# FTDI.net
KiCad netlist of a schematic drawn in Altium Designer
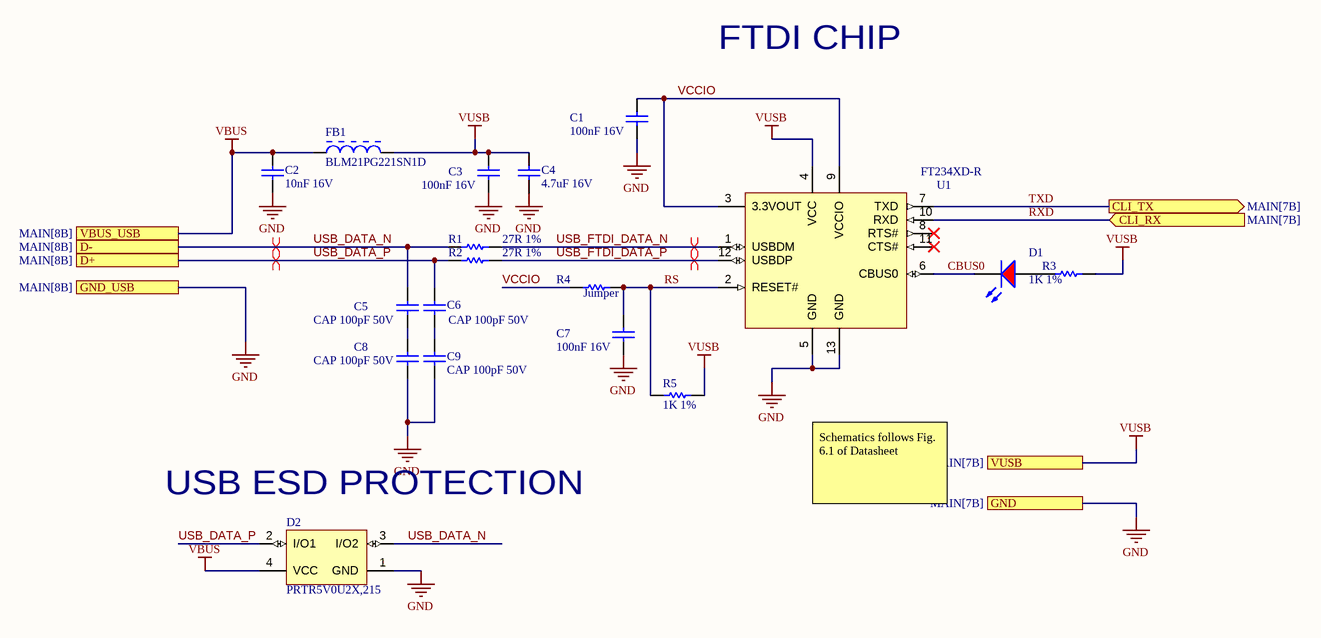
[diagram p0: FTDI.SchDoc]

(export (version "E")
  (design (tool "Eeschema 10.0.6"))
  (components
    (comp (ref "C1")
      (value "100nF 16V")
      (footprint "CAPC0603(1608)100_N")
      (description "CAP 100nF 16V ±10% 0603 (1608 Metric) Thickness 1mm SMD")
      (fields (field (name "TOLERANCE") "Â±10%"))
      (libsource (lib "Altium Content Vault") (part "CAP"))
    )
    (comp (ref "C2")
      (value "10nF 16V")
      (footprint "CAPC0603(1608)100_N")
      (description "CAP 10nF 16V ±10% 0603 (1608 Metric) Thickness 1mm SMD")
      (fields (field (name "TOLERANCE") "Â±10%"))
      (libsource (lib "Altium Content Vault") (part "CAP"))
    )
    (comp (ref "C3")
      (value "100nF 16V")
      (footprint "CAPC0603(1608)100_N")
      (description "CAP 100nF 16V ±10% 0603 (1608 Metric) Thickness 1mm SMD")
      (fields (field (name "TOLERANCE") "Â±10%"))
      (libsource (lib "Altium Content Vault") (part "CAP"))
    )
    (comp (ref "C4")
      (value "4.7uF 16V")
      (footprint "CAPC0805(2012)145_N")
      (description "CAP 4.7uF 16V -20% to +80% 0805 (2012 Metric) Thickness 1.45mm SMD")
      (fields (field (name "TOLERANCE") "-20% to +80%"))
      (libsource (lib "Altium Content Vault") (part "CAP"))
    )
    (comp (ref "C5")
      (value "CAP 100pF 50V")
      (footprint "CAPC0603(1608)100_L")
      (description "CAP 100pF 50V ±20% 0603 (1608 Metric) Thickness 1mm SMD")
      (fields (field (name "TOLERANCE") "Â±20%"))
      (libsource (lib "Altium Content Vault") (part "CAP"))
    )
    (comp (ref "C6")
      (value "CAP 100pF 50V")
      (footprint "CAPC0603(1608)100_L")
      (description "CAP 100pF 50V ±20% 0603 (1608 Metric) Thickness 1mm SMD")
      (fields (field (name "TOLERANCE") "Â±20%"))
      (libsource (lib "Altium Content Vault") (part "CAP"))
    )
    (comp (ref "C7")
      (value "100nF 16V")
      (footprint "CAPC0603(1608)100_N")
      (description "CAP 100nF 16V ±10% 0603 (1608 Metric) Thickness 1mm SMD")
      (fields (field (name "TOLERANCE") "Â±10%"))
      (libsource (lib "Altium Content Vault") (part "CAP"))
    )
    (comp (ref "C8")
      (value "CAP 100pF 50V")
      (footprint "CAPC0603(1608)100_L")
      (description "CAP 100pF 50V ±20% 0603 (1608 Metric) Thickness 1mm SMD")
      (fields (field (name "TOLERANCE") "Â±20%"))
      (libsource (lib "Altium Content Vault") (part "CAP"))
    )
    (comp (ref "C9")
      (value "CAP 100pF 50V")
      (footprint "CAPC0603(1608)100_L")
      (description "CAP 100pF 50V ±20% 0603 (1608 Metric) Thickness 1mm SMD")
      (fields (field (name "TOLERANCE") "Â±20%"))
      (libsource (lib "Altium Content Vault") (part "CAP"))
    )
    (comp (ref "D1")
      (value "LTST-C170CKT")
      (footprint "LTST-C170CKT_V")
      (description "LED Uni-Color Red, 100 mW, 200 mA, -55 to 85 degC, 2-Pin SMD, RoHS, Tape and Reel")
      (fields (field (name "MANUFACTURER") "Lite-On"))
      (libsource (lib "Altium Content Vault") (part "LED-RED-AK-2"))
    )
    (comp (ref "D2")
      (value "PRTR5V0U2X,215")
      (footprint "NXP-SOT143B-4_V")
      (fields (field (name "MANUFACTURER") "NXP Semiconductors"))
      (libsource (lib "Altium Content Vault") (part "NXP-PRTR5V0U2X,215-4"))
    )
    (comp (ref "FB1")
      (value "BLM21PG221SN1D")
      (footprint "MURA-BLM21-B20-CHIP-2_V2")
      (fields (field (name "MANUFACTURER") "Murata"))
      (libsource (lib "Altium Content Vault") (part "MURA-FB-2"))
    )
    (comp (ref "R1")
      (value "27R 1%")
      (footprint "RESC0603(1608)_N")
      (description "27R 0.1W 1% 0603 (1608 Metric)  SMD")
      (fields (field (name "TOLERANCE") "1 %") (field (name "POWER") "0.1 W"))
      (libsource (lib "Altium Content Vault") (part "RES"))
    )
    (comp (ref "R2")
      (value "27R 1%")
      (footprint "RESC0603(1608)_N")
      (description "27R 0.1W 1% 0603 (1608 Metric)  SMD")
      (fields (field (name "TOLERANCE") "1 %") (field (name "POWER") "0.1 W"))
      (libsource (lib "Altium Content Vault") (part "RES"))
    )
    (comp (ref "R3")
      (value "1K 1%")
      (footprint "RESC0603(1608)_N")
      (description "1K 0.1W 1% 0603 (1608 Metric)  SMD")
      (fields (field (name "TOLERANCE") "1 %") (field (name "POWER") "0.1 W"))
      (libsource (lib "Altium Content Vault") (part "RES"))
    )
    (comp (ref "R4")
      (value "Jumper")
      (footprint "RESC0603(1608)_N")
      (description "Jumper 0603 (1608 Metric)")
      (fields (field (name "POWER") "None"))
      (libsource (lib "Altium Content Vault") (part "RES"))
    )
    (comp (ref "R5")
      (value "1K 1%")
      (footprint "RESC0603(1608)_N")
      (description "1K 0.1W 1% 0603 (1608 Metric)  SMD")
      (fields (field (name "TOLERANCE") "1 %") (field (name "POWER") "0.1 W"))
      (libsource (lib "Altium Content Vault") (part "RES"))
    )
    (comp (ref "U1")
      (value "FT234XD-R")
      (footprint "DFN-12_V")
      (description "FT234XD USB to BASIC UART IC, -40 to +85 degC, 12-Pin DFN, Pb-Free, Tape and Reel")
      (fields (field (name "MANUFACTURER") "FTDI"))
      (libsource (lib "Altium Content Vault") (part "FTDI-FT234XD-DFN-12"))
    )
  )
  (nets
    (net (code "1") (name "/CBUS0") (class "Default")
      (node (ref "D1") (pin "2") (pinfunction "K_2") (pintype "passive"))
      (node (ref "U1") (pin "6") (pinfunction "CBUS0_6") (pintype "bidirectional"))
    )
    (net (code "2") (name "/RS") (class "Default")
      (node (ref "C7") (pin "2") (pinfunction "2_2") (pintype "passive"))
      (node (ref "R4") (pin "2") (pinfunction "2_2") (pintype "passive"))
      (node (ref "R5") (pin "2") (pinfunction "2_2") (pintype "passive"))
      (node (ref "U1") (pin "2") (pinfunction "RESET#_2") (pintype "input"))
    )
    (net (code "3") (name "/RXD") (class "Default")
      (node (ref "U1") (pin "10") (pinfunction "RXD_10") (pintype "input"))
    )
    (net (code "4") (name "/TXD") (class "Default")
      (node (ref "U1") (pin "7") (pinfunction "TXD_7") (pintype "output"))
    )
    (net (code "5") (name "/USB_DATA_N") (class "Default")
      (node (ref "C5") (pin "2") (pinfunction "2_2") (pintype "passive"))
      (node (ref "D2") (pin "3") (pinfunction "I/O2_3") (pintype "bidirectional"))
      (node (ref "R1") (pin "1") (pinfunction "1_1") (pintype "passive"))
    )
    (net (code "6") (name "/USB_DATA_P") (class "Default")
      (node (ref "C6") (pin "2") (pinfunction "2_2") (pintype "passive"))
      (node (ref "D2") (pin "2") (pinfunction "I/O1_2") (pintype "bidirectional"))
      (node (ref "R2") (pin "1") (pinfunction "1_1") (pintype "passive"))
    )
    (net (code "7") (name "/USB_FTDI_DATA_N") (class "Default")
      (node (ref "R1") (pin "2") (pinfunction "2_2") (pintype "passive"))
      (node (ref "U1") (pin "1") (pinfunction "USBDM_1") (pintype "bidirectional"))
    )
    (net (code "8") (name "/USB_FTDI_DATA_P") (class "Default")
      (node (ref "R2") (pin "2") (pinfunction "2_2") (pintype "passive"))
      (node (ref "U1") (pin "12") (pinfunction "USBDP_12") (pintype "bidirectional"))
    )
    (net (code "9") (name "/VCCIO") (class "Default")
      (node (ref "C1") (pin "2") (pinfunction "2_2") (pintype "passive"))
      (node (ref "R4") (pin "1") (pinfunction "1_1") (pintype "passive"))
      (node (ref "U1") (pin "3") (pinfunction "3.3VOUT_3") (pintype "power_in"))
      (node (ref "U1") (pin "9") (pinfunction "VCCIO_9") (pintype "power_in"))
    )
    (net (code "10") (name "GND") (class "Default")
      (node (ref "C1") (pin "1") (pinfunction "1_1") (pintype "passive"))
      (node (ref "C2") (pin "1") (pinfunction "1_1") (pintype "passive"))
      (node (ref "C3") (pin "1") (pinfunction "1_1") (pintype "passive"))
      (node (ref "C4") (pin "1") (pinfunction "1_1") (pintype "passive"))
      (node (ref "C7") (pin "1") (pinfunction "1_1") (pintype "passive"))
      (node (ref "C8") (pin "1") (pinfunction "1_1") (pintype "passive"))
      (node (ref "C9") (pin "1") (pinfunction "1_1") (pintype "passive"))
      (node (ref "D2") (pin "1") (pinfunction "GND_1") (pintype "power_in"))
      (node (ref "U1") (pin "13") (pinfunction "GND_13") (pintype "power_in"))
      (node (ref "U1") (pin "5") (pinfunction "GND_5") (pintype "power_in"))
    )
    (net (code "11") (name "Net-(C5-Pad1)") (class "Default")
      (node (ref "C5") (pin "1") (pinfunction "1_1") (pintype "passive"))
      (node (ref "C8") (pin "2") (pinfunction "2_2") (pintype "passive"))
    )
    (net (code "12") (name "Net-(C6-Pad1)") (class "Default")
      (node (ref "C6") (pin "1") (pinfunction "1_1") (pintype "passive"))
      (node (ref "C9") (pin "2") (pinfunction "2_2") (pintype "passive"))
    )
    (net (code "13") (name "Net-(D1-A)") (class "Default")
      (node (ref "D1") (pin "1") (pinfunction "A_1") (pintype "passive"))
      (node (ref "R3") (pin "1") (pinfunction "1_1") (pintype "passive"))
    )
    (net (code "14") (name "VBUS") (class "Default")
      (node (ref "C2") (pin "2") (pinfunction "2_2") (pintype "passive"))
      (node (ref "D2") (pin "4") (pinfunction "VCC_4") (pintype "power_in"))
      (node (ref "FB1") (pin "1") (pinfunction "1_1") (pintype "passive"))
    )
    (net (code "15") (name "VUSB") (class "Default")
      (node (ref "C3") (pin "2") (pinfunction "2_2") (pintype "passive"))
      (node (ref "C4") (pin "2") (pinfunction "2_2") (pintype "passive"))
      (node (ref "FB1") (pin "2") (pinfunction "2_2") (pintype "passive"))
      (node (ref "R3") (pin "2") (pinfunction "2_2") (pintype "passive"))
      (node (ref "R5") (pin "1") (pinfunction "1_1") (pintype "passive"))
      (node (ref "U1") (pin "4") (pinfunction "VCC_4") (pintype "power_in"))
    )
    (net (code "16") (name "unconnected-(U1-CTS#-Pad11)") (class "Default")
      (node (ref "U1") (pin "11") (pinfunction "CTS#_11") (pintype "input+no_connect"))
    )
    (net (code "17") (name "unconnected-(U1-RTS#-Pad8)") (class "Default")
      (node (ref "U1") (pin "8") (pinfunction "RTS#_8") (pintype "output+no_connect"))
    )
  )
)
